# Logic.net
KiCad netlist of a schematic drawn in Altium Designer
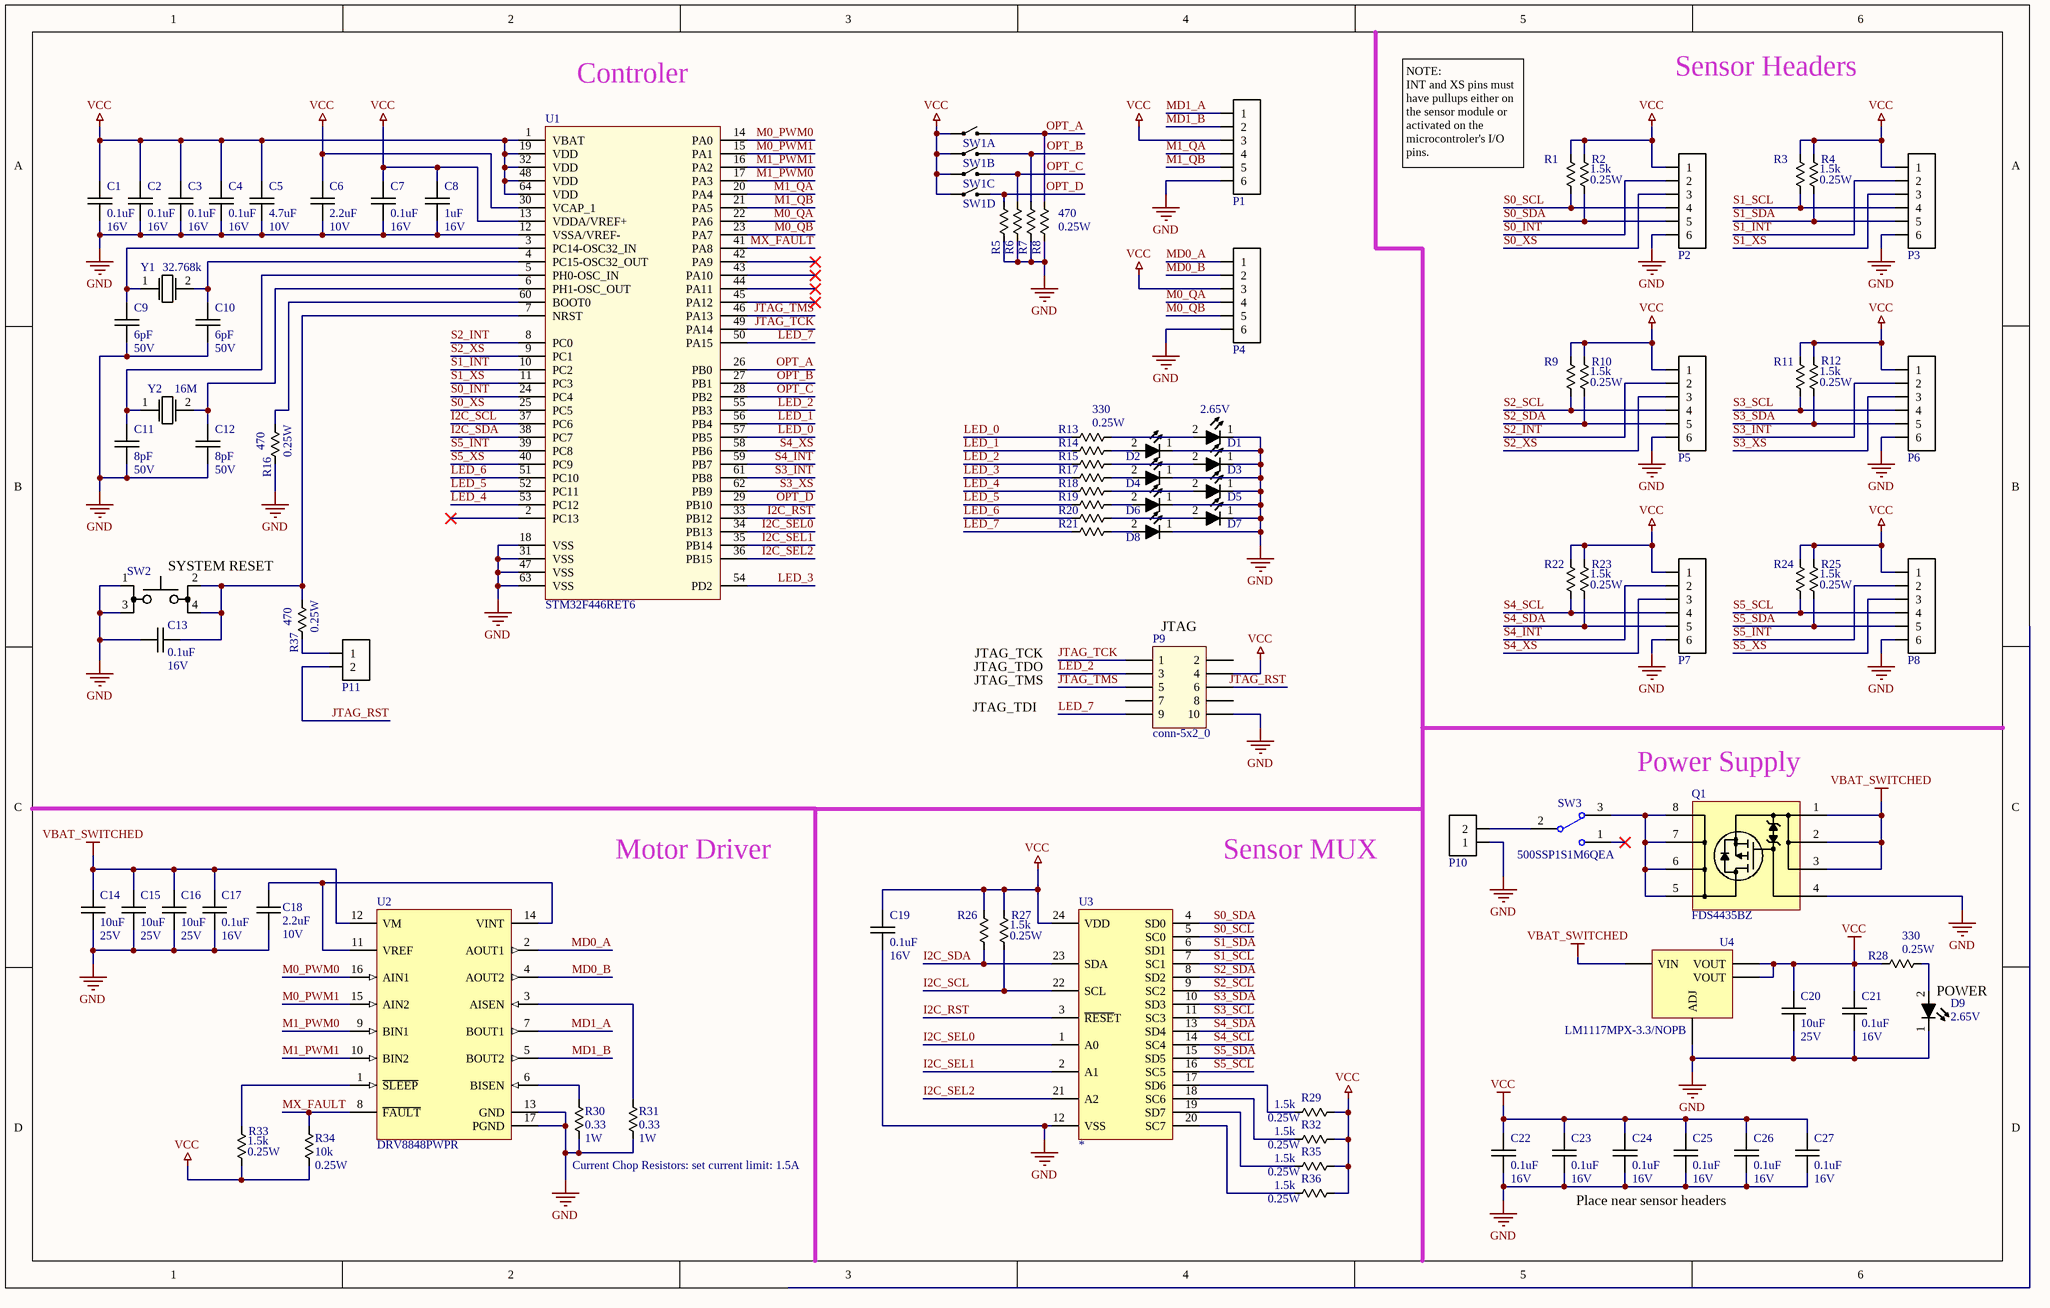
[diagram p0: Logic.SchDoc]

(export (version "E")
  (design (tool "Eeschema 10.0.6"))
  (components
    (comp (ref "C1")
      (value "cap_single_np")
      (footprint "chip_0603")
      (description "CAP, 0.1uF, ±10%, 16V, X7R, 0603")
      (fields
        (field (name "TOLERANCE") "±10%")
        (field (name "CAPACITANCE") "0.1uF")
        (field (name "VOLTAGE RATING") "16V")
        (field (name "PART NUMBER") "CAP-00542")
      )
      (libsource (lib "Capacitors") (part "cap_single_np"))
    )
    (comp (ref "C2")
      (value "cap_single_np")
      (footprint "chip_0603")
      (description "CAP, 0.1uF, ±10%, 16V, X7R, 0603")
      (fields
        (field (name "TOLERANCE") "±10%")
        (field (name "CAPACITANCE") "0.1uF")
        (field (name "VOLTAGE RATING") "16V")
        (field (name "PART NUMBER") "CAP-00542")
      )
      (libsource (lib "Capacitors") (part "cap_single_np"))
    )
    (comp (ref "C3")
      (value "cap_single_np")
      (footprint "chip_0603")
      (description "CAP, 0.1uF, ±10%, 16V, X7R, 0603")
      (fields
        (field (name "TOLERANCE") "±10%")
        (field (name "CAPACITANCE") "0.1uF")
        (field (name "VOLTAGE RATING") "16V")
        (field (name "PART NUMBER") "CAP-00542")
      )
      (libsource (lib "Capacitors") (part "cap_single_np"))
    )
    (comp (ref "C4")
      (value "cap_single_np")
      (footprint "chip_0603")
      (description "CAP, 0.1uF, ±10%, 16V, X7R, 0603")
      (fields
        (field (name "TOLERANCE") "±10%")
        (field (name "CAPACITANCE") "0.1uF")
        (field (name "VOLTAGE RATING") "16V")
        (field (name "PART NUMBER") "CAP-00542")
      )
      (libsource (lib "Capacitors") (part "cap_single_np"))
    )
    (comp (ref "C5")
      (value "cap_single_np")
      (footprint "chip_0805")
      (description "CAP, 4.7uF, 10%, 10V, X7R, 0805")
      (fields
        (field (name "TOLERANCE") "10%")
        (field (name "CAPACITANCE") "4.7uF")
        (field (name "VOLTAGE RATING") "10V")
        (field (name "PART NUMBER") "CAP-00126")
      )
      (libsource (lib "Capacitors") (part "cap_single_np"))
    )
    (comp (ref "C6")
      (value "cap_single_np")
      (footprint "chip_0603")
      (description "CAP, 2.2uF, ±10%, 10V, X7R, 0603")
      (fields
        (field (name "TOLERANCE") "±10%")
        (field (name "CAPACITANCE") "2.2uF")
        (field (name "VOLTAGE RATING") "10V")
        (field (name "PART NUMBER") "CAP-00531")
      )
      (libsource (lib "Capacitors") (part "cap_single_np"))
    )
    (comp (ref "C7")
      (value "cap_single_np")
      (footprint "chip_0603")
      (description "CAP, 0.1uF, ±10%, 16V, X7R, 0603")
      (fields
        (field (name "TOLERANCE") "±10%")
        (field (name "CAPACITANCE") "0.1uF")
        (field (name "VOLTAGE RATING") "16V")
        (field (name "PART NUMBER") "CAP-00542")
      )
      (libsource (lib "Capacitors") (part "cap_single_np"))
    )
    (comp (ref "C8")
      (value "cap_single_np")
      (footprint "chip_0805")
      (description "CAP, 1uF, 10%, 16V, X7R, 0805")
      (fields
        (field (name "TOLERANCE") "10%")
        (field (name "CAPACITANCE") "1uF")
        (field (name "VOLTAGE RATING") "16V")
        (field (name "PART NUMBER") "CAP-00107")
      )
      (libsource (lib "Capacitors") (part "cap_single_np"))
    )
    (comp (ref "C9")
      (value "cap_single_np")
      (footprint "chip_0603")
      (description "CAP, 6pF, ±10%, 50V, C0G, 0603")
      (fields
        (field (name "TOLERANCE") "±10%")
        (field (name "CAPACITANCE") "6pF")
        (field (name "VOLTAGE RATING") "50V")
        (field (name "PART NUMBER") "CAP-00538")
      )
      (libsource (lib "Capacitors") (part "cap_single_np"))
    )
    (comp (ref "C10")
      (value "cap_single_np")
      (footprint "chip_0603")
      (description "CAP, 6pF, ±10%, 50V, C0G, 0603")
      (fields
        (field (name "TOLERANCE") "±10%")
        (field (name "CAPACITANCE") "6pF")
        (field (name "VOLTAGE RATING") "50V")
        (field (name "PART NUMBER") "CAP-00538")
      )
      (libsource (lib "Capacitors") (part "cap_single_np"))
    )
    (comp (ref "C11")
      (value "cap_single_np")
      (footprint "chip_0603")
      (description "CAP, 8pF, ±0.1pF, 50V, C0G, 0603")
      (fields
        (field (name "TOLERANCE") "±0.1pF")
        (field (name "CAPACITANCE") "8pF")
        (field (name "VOLTAGE RATING") "50V")
        (field (name "PART NUMBER") "CAP-00402")
      )
      (libsource (lib "Capacitors") (part "cap_single_np"))
    )
    (comp (ref "C12")
      (value "cap_single_np")
      (footprint "chip_0603")
      (description "CAP, 8pF, ±0.1pF, 50V, C0G, 0603")
      (fields
        (field (name "TOLERANCE") "±0.1pF")
        (field (name "CAPACITANCE") "8pF")
        (field (name "VOLTAGE RATING") "50V")
        (field (name "PART NUMBER") "CAP-00402")
      )
      (libsource (lib "Capacitors") (part "cap_single_np"))
    )
    (comp (ref "C13")
      (value "cap_single_np")
      (footprint "chip_0603")
      (description "CAP, 0.1uF, ±10%, 16V, X7R, 0603")
      (fields
        (field (name "TOLERANCE") "±10%")
        (field (name "CAPACITANCE") "0.1uF")
        (field (name "VOLTAGE RATING") "16V")
        (field (name "PART NUMBER") "CAP-00542")
      )
      (libsource (lib "Capacitors") (part "cap_single_np"))
    )
    (comp (ref "C14")
      (value "cap_single_np")
      (footprint "chip_1206")
      (description "CAP, 10uF, ±10%, 25V, X7R, 1206")
      (fields
        (field (name "TOLERANCE") "±10%")
        (field (name "CAPACITANCE") "10uF")
        (field (name "VOLTAGE RATING") "25V")
        (field (name "PART NUMBER") "CAP-00539")
      )
      (libsource (lib "Capacitors") (part "cap_single_np"))
    )
    (comp (ref "C15")
      (value "cap_single_np")
      (footprint "chip_1206")
      (description "CAP, 10uF, ±10%, 25V, X7R, 1206")
      (fields
        (field (name "TOLERANCE") "±10%")
        (field (name "CAPACITANCE") "10uF")
        (field (name "VOLTAGE RATING") "25V")
        (field (name "PART NUMBER") "CAP-00539")
      )
      (libsource (lib "Capacitors") (part "cap_single_np"))
    )
    (comp (ref "C16")
      (value "cap_single_np")
      (footprint "chip_1206")
      (description "CAP, 10uF, ±10%, 25V, X7R, 1206")
      (fields
        (field (name "TOLERANCE") "±10%")
        (field (name "CAPACITANCE") "10uF")
        (field (name "VOLTAGE RATING") "25V")
        (field (name "PART NUMBER") "CAP-00539")
      )
      (libsource (lib "Capacitors") (part "cap_single_np"))
    )
    (comp (ref "C17")
      (value "cap_single_np")
      (footprint "chip_0603")
      (description "CAP, 0.1uF, ±10%, 16V, X7R, 0603")
      (fields
        (field (name "TOLERANCE") "±10%")
        (field (name "CAPACITANCE") "0.1uF")
        (field (name "VOLTAGE RATING") "16V")
        (field (name "PART NUMBER") "CAP-00542")
      )
      (libsource (lib "Capacitors") (part "cap_single_np"))
    )
    (comp (ref "C18")
      (value "cap_single_np")
      (footprint "chip_0603")
      (description "CAP, 2.2uF, ±10%, 10V, X7R, 0603")
      (fields
        (field (name "TOLERANCE") "±10%")
        (field (name "CAPACITANCE") "2.2uF")
        (field (name "VOLTAGE RATING") "10V")
        (field (name "PART NUMBER") "CAP-00531")
      )
      (libsource (lib "Capacitors") (part "cap_single_np"))
    )
    (comp (ref "C19")
      (value "cap_single_np")
      (footprint "chip_0603")
      (description "CAP, 0.1uF, ±10%, 16V, X7R, 0603")
      (fields
        (field (name "TOLERANCE") "±10%")
        (field (name "CAPACITANCE") "0.1uF")
        (field (name "VOLTAGE RATING") "16V")
        (field (name "PART NUMBER") "CAP-00542")
      )
      (libsource (lib "Capacitors") (part "cap_single_np"))
    )
    (comp (ref "C20")
      (value "cap_single_np")
      (footprint "chip_1206")
      (description "CAP, 10uF, ±10%, 25V, X7R, 1206")
      (fields
        (field (name "TOLERANCE") "±10%")
        (field (name "CAPACITANCE") "10uF")
        (field (name "VOLTAGE RATING") "25V")
        (field (name "PART NUMBER") "CAP-00539")
      )
      (libsource (lib "Capacitors") (part "cap_single_np"))
    )
    (comp (ref "C21")
      (value "cap_single_np")
      (footprint "chip_0603")
      (description "CAP, 0.1uF, ±10%, 16V, X7R, 0603")
      (fields
        (field (name "TOLERANCE") "±10%")
        (field (name "CAPACITANCE") "0.1uF")
        (field (name "VOLTAGE RATING") "16V")
        (field (name "PART NUMBER") "CAP-00542")
      )
      (libsource (lib "Capacitors") (part "cap_single_np"))
    )
    (comp (ref "C22")
      (value "cap_single_np")
      (footprint "chip_0603")
      (description "CAP, 0.1uF, ±10%, 16V, X7R, 0603")
      (fields
        (field (name "TOLERANCE") "±10%")
        (field (name "CAPACITANCE") "0.1uF")
        (field (name "VOLTAGE RATING") "16V")
        (field (name "PART NUMBER") "CAP-00542")
      )
      (libsource (lib "Capacitors") (part "cap_single_np"))
    )
    (comp (ref "C23")
      (value "cap_single_np")
      (footprint "chip_0603")
      (description "CAP, 0.1uF, ±10%, 16V, X7R, 0603")
      (fields
        (field (name "TOLERANCE") "±10%")
        (field (name "CAPACITANCE") "0.1uF")
        (field (name "VOLTAGE RATING") "16V")
        (field (name "PART NUMBER") "CAP-00542")
      )
      (libsource (lib "Capacitors") (part "cap_single_np"))
    )
    (comp (ref "C24")
      (value "cap_single_np")
      (footprint "chip_0603")
      (description "CAP, 0.1uF, ±10%, 16V, X7R, 0603")
      (fields
        (field (name "TOLERANCE") "±10%")
        (field (name "CAPACITANCE") "0.1uF")
        (field (name "VOLTAGE RATING") "16V")
        (field (name "PART NUMBER") "CAP-00542")
      )
      (libsource (lib "Capacitors") (part "cap_single_np"))
    )
    (comp (ref "C25")
      (value "cap_single_np")
      (footprint "chip_0603")
      (description "CAP, 0.1uF, ±10%, 16V, X7R, 0603")
      (fields
        (field (name "TOLERANCE") "±10%")
        (field (name "CAPACITANCE") "0.1uF")
        (field (name "VOLTAGE RATING") "16V")
        (field (name "PART NUMBER") "CAP-00542")
      )
      (libsource (lib "Capacitors") (part "cap_single_np"))
    )
    (comp (ref "C26")
      (value "cap_single_np")
      (footprint "chip_0603")
      (description "CAP, 0.1uF, ±10%, 16V, X7R, 0603")
      (fields
        (field (name "TOLERANCE") "±10%")
        (field (name "CAPACITANCE") "0.1uF")
        (field (name "VOLTAGE RATING") "16V")
        (field (name "PART NUMBER") "CAP-00542")
      )
      (libsource (lib "Capacitors") (part "cap_single_np"))
    )
    (comp (ref "C27")
      (value "cap_single_np")
      (footprint "chip_0603")
      (description "CAP, 0.1uF, ±10%, 16V, X7R, 0603")
      (fields
        (field (name "TOLERANCE") "±10%")
        (field (name "CAPACITANCE") "0.1uF")
        (field (name "VOLTAGE RATING") "16V")
        (field (name "PART NUMBER") "CAP-00542")
      )
      (libsource (lib "Capacitors") (part "cap_single_np"))
    )
    (comp (ref "D1")
      (value "diode_4")
      (footprint "chip_0603")
      (description "LED, Green, 0603, Low current, HELI2 Series")
      (fields
        (field (name "FORWARD VOLTAGE") "2.65V")
        (field (name "PART NUMBER") "DIO-00050")
        (field (name "MANUFACTURER") "Kingbright")
      )
      (libsource (lib "Diodes") (part "diode_4"))
    )
    (comp (ref "D2")
      (value "diode_4")
      (footprint "chip_0603")
      (description "LED, Green, 0603, Low current, HELI2 Series")
      (fields (field (name "PART NUMBER") "DIO-00050") (field (name "MANUFACTURER") "Kingbright"))
      (libsource (lib "Diodes") (part "diode_4"))
    )
    (comp (ref "D3")
      (value "diode_4")
      (footprint "chip_0603")
      (description "LED, Green, 0603, Low current, HELI2 Series")
      (fields (field (name "PART NUMBER") "DIO-00050") (field (name "MANUFACTURER") "Kingbright"))
      (libsource (lib "Diodes") (part "diode_4"))
    )
    (comp (ref "D4")
      (value "diode_4")
      (footprint "chip_0603")
      (description "LED, Green, 0603, Low current, HELI2 Series")
      (fields (field (name "PART NUMBER") "DIO-00050") (field (name "MANUFACTURER") "Kingbright"))
      (libsource (lib "Diodes") (part "diode_4"))
    )
    (comp (ref "D5")
      (value "diode_4")
      (footprint "chip_0603")
      (description "LED, Green, 0603, Low current, HELI2 Series")
      (fields (field (name "PART NUMBER") "DIO-00050") (field (name "MANUFACTURER") "Kingbright"))
      (libsource (lib "Diodes") (part "diode_4"))
    )
    (comp (ref "D6")
      (value "diode_4")
      (footprint "chip_0603")
      (description "LED, Green, 0603, Low current, HELI2 Series")
      (fields (field (name "PART NUMBER") "DIO-00050") (field (name "MANUFACTURER") "Kingbright"))
      (libsource (lib "Diodes") (part "diode_4"))
    )
    (comp (ref "D7")
      (value "diode_4")
      (footprint "chip_0603")
      (description "LED, Green, 0603, Low current, HELI2 Series")
      (fields (field (name "PART NUMBER") "DIO-00050") (field (name "MANUFACTURER") "Kingbright"))
      (libsource (lib "Diodes") (part "diode_4"))
    )
    (comp (ref "D8")
      (value "diode_4")
      (footprint "chip_0603")
      (description "LED, Green, 0603, Low current, HELI2 Series")
      (fields (field (name "PART NUMBER") "DIO-00050") (field (name "MANUFACTURER") "Kingbright"))
      (libsource (lib "Diodes") (part "diode_4"))
    )
    (comp (ref "D9")
      (value "diode_4")
      (footprint "chip_0603")
      (description "LED, Blue, 0603, Low current, HELI2 Series")
      (fields
        (field (name "FORWARD VOLTAGE") "2.65V")
        (field (name "PART NUMBER") "DIO-00049")
        (field (name "MANUFACTURER") "Kingbright")
      )
      (libsource (lib "Diodes") (part "diode_4"))
    )
    (comp (ref "P1")
      (value "conn-6x1_0")
      (footprint "JST_PHR_6_0")
      (description "JST PHR 6x1")
      (fields (field (name "PART NUMBER") "CONN-00017") (field (name "MANUFACTURER") "JST"))
      (libsource (lib "Connectors") (part "conn-6x1_0"))
    )
    (comp (ref "P2")
      (value "conn-6x1_0")
      (footprint "HDDR_6X1_0")
      (description "Header 6x1, 0.1\"")
      (fields (field (name "PART NUMBER") "CONN-00008"))
      (libsource (lib "Connectors") (part "conn-6x1_0"))
    )
    (comp (ref "P3")
      (value "conn-6x1_0")
      (footprint "HDDR_6X1_0")
      (description "Header 6x1, 0.1\"")
      (fields (field (name "PART NUMBER") "CONN-00008"))
      (libsource (lib "Connectors") (part "conn-6x1_0"))
    )
    (comp (ref "P4")
      (value "conn-6x1_0")
      (footprint "JST_PHR_6_0")
      (description "JST PHR 6x1")
      (fields (field (name "PART NUMBER") "CONN-00017") (field (name "MANUFACTURER") "JST"))
      (libsource (lib "Connectors") (part "conn-6x1_0"))
    )
    (comp (ref "P5")
      (value "conn-6x1_0")
      (footprint "HDDR_6X1_0")
      (description "Header 6x1, 0.1\"")
      (fields (field (name "PART NUMBER") "CONN-00008"))
      (libsource (lib "Connectors") (part "conn-6x1_0"))
    )
    (comp (ref "P6")
      (value "conn-6x1_0")
      (footprint "HDDR_6X1_0")
      (description "Header 6x1, 0.1\"")
      (fields (field (name "PART NUMBER") "CONN-00008"))
      (libsource (lib "Connectors") (part "conn-6x1_0"))
    )
    (comp (ref "P7")
      (value "conn-6x1_0")
      (footprint "HDDR_6X1_0")
      (description "Header 6x1, 0.1\"")
      (fields (field (name "PART NUMBER") "CONN-00008"))
      (libsource (lib "Connectors") (part "conn-6x1_0"))
    )
    (comp (ref "P8")
      (value "conn-6x1_0")
      (footprint "HDDR_6X1_0")
      (description "Header 6x1, 0.1\"")
      (fields (field (name "PART NUMBER") "CONN-00008"))
      (libsource (lib "Connectors") (part "conn-6x1_0"))
    )
    (comp (ref "P9")
      (value "conn-5x2_0")
      (footprint "CNC_TECH_3020-10-0100-XX")
      (description "Header, 10-pin IDC, 2.54mm Pitch")
      (fields (field (name "PART NUMBER") "CONN-00054") (field (name "MANUFACTURER") "CNC Tech"))
      (libsource (lib "Connectors") (part "conn-5x2_0"))
    )
    (comp (ref "P10")
      (value "conn-2x1_0")
      (footprint "PHOENIX_MKDS_5.08MM_2x1")
      (description "Term Blk, 2 Pos, 0.2\", 10A, 14-30 AWG, Rising Cage Clamp")
      (fields (field (name "PART NUMBER") "CONN-00014") (field (name "MANUFACTURER") "Phoenix Contact"))
      (libsource (lib "Connectors") (part "conn-2x1_0"))
    )
    (comp (ref "P11")
      (value "conn-2x1_0")
      (footprint "hddr_2x1_0")
      (description "Header, 2x1, 0.1\"")
      (fields (field (name "PART NUMBER") "CONN-00055") (field (name "MANUFACTURER") "Samtec"))
      (libsource (lib "Connectors") (part "conn-2x1_0"))
    )
    (comp (ref "Q1")
      (value "p-mosfet-SSSGDDDD")
      (footprint "SO-8")
      (description "XSTR PFET, 8.8A, 30V, 2.5W, SOIC-8")
      (fields
        (field (name "MANUFACTURER PN") "FDS4435BZ")
        (field (name "PART NUMBER") "XSTR-00033")
        (field (name "MANUFACTURER") "ON Semi")
      )
      (libsource (lib "Transistors") (part "p-mosfet-SSSGDDDD"))
    )
    (comp (ref "R1")
      (value "res_single")
      (footprint "chip_0603")
      (description "RES SMD 1.5K OHM 1% 1/4W 0603")
      (fields (field (name "TOLERANCE") "1%") (field (name "PART NUMBER") "RES-00284"))
      (libsource (lib "Resistors") (part "res_single"))
    )
    (comp (ref "R2")
      (value "res_single")
      (footprint "chip_0603")
      (description "RES SMD 1.5K OHM 1% 1/4W 0603")
      (fields
        (field (name "TOLERANCE") "1%")
        (field (name "RESISTANCE") "1.5k")
        (field (name "POWER RATING") "0.25W")
        (field (name "PART NUMBER") "RES-00284")
      )
      (libsource (lib "Resistors") (part "res_single"))
    )
    (comp (ref "R3")
      (value "res_single")
      (footprint "chip_0603")
      (description "RES SMD 1.5K OHM 1% 1/4W 0603")
      (fields (field (name "TOLERANCE") "1%") (field (name "PART NUMBER") "RES-00284"))
      (libsource (lib "Resistors") (part "res_single"))
    )
    (comp (ref "R4")
      (value "res_single")
      (footprint "chip_0603")
      (description "RES SMD 1.5K OHM 1% 1/4W 0603")
      (fields
        (field (name "TOLERANCE") "1%")
        (field (name "RESISTANCE") "1.5k")
        (field (name "POWER RATING") "0.25W")
        (field (name "PART NUMBER") "RES-00284")
      )
      (libsource (lib "Resistors") (part "res_single"))
    )
    (comp (ref "R5")
      (value "res_single")
      (footprint "chip_0603")
      (description "RES SMD 470 OHM 1% 1/4W 0603")
      (fields (field (name "TOLERANCE") "1%") (field (name "PART NUMBER") "RES-00236"))
      (libsource (lib "Resistors") (part "res_single"))
    )
    (comp (ref "R6")
      (value "res_single")
      (footprint "chip_0603")
      (description "RES SMD 470 OHM 1% 1/4W 0603")
      (fields (field (name "TOLERANCE") "1%") (field (name "PART NUMBER") "RES-00236"))
      (libsource (lib "Resistors") (part "res_single"))
    )
    (comp (ref "R7")
      (value "res_single")
      (footprint "chip_0603")
      (description "RES SMD 470 OHM 1% 1/4W 0603")
      (fields (field (name "TOLERANCE") "1%") (field (name "PART NUMBER") "RES-00236"))
      (libsource (lib "Resistors") (part "res_single"))
    )
    (comp (ref "R8")
      (value "res_single")
      (footprint "chip_0603")
      (description "RES SMD 470 OHM 1% 1/4W 0603")
      (fields
        (field (name "TOLERANCE") "1%")
        (field (name "RESISTANCE") "470")
        (field (name "POWER RATING") "0.25W")
        (field (name "PART NUMBER") "RES-00236")
      )
      (libsource (lib "Resistors") (part "res_single"))
    )
    (comp (ref "R9")
      (value "res_single")
      (footprint "chip_0603")
      (description "RES SMD 1.5K OHM 1% 1/4W 0603")
      (fields (field (name "TOLERANCE") "1%") (field (name "PART NUMBER") "RES-00284"))
      (libsource (lib "Resistors") (part "res_single"))
    )
    (comp (ref "R10")
      (value "res_single")
      (footprint "chip_0603")
      (description "RES SMD 1.5K OHM 1% 1/4W 0603")
      (fields
        (field (name "TOLERANCE") "1%")
        (field (name "RESISTANCE") "1.5k")
        (field (name "POWER RATING") "0.25W")
        (field (name "PART NUMBER") "RES-00284")
      )
      (libsource (lib "Resistors") (part "res_single"))
    )
    (comp (ref "R11")
      (value "res_single")
      (footprint "chip_0603")
      (description "RES SMD 1.5K OHM 1% 1/4W 0603")
      (fields (field (name "TOLERANCE") "1%") (field (name "PART NUMBER") "RES-00284"))
      (libsource (lib "Resistors") (part "res_single"))
    )
    (comp (ref "R12")
      (value "res_single")
      (footprint "chip_0603")
      (description "RES SMD 1.5K OHM 1% 1/4W 0603")
      (fields
        (field (name "TOLERANCE") "1%")
        (field (name "RESISTANCE") "1.5k")
        (field (name "POWER RATING") "0.25W")
        (field (name "PART NUMBER") "RES-00284")
      )
      (libsource (lib "Resistors") (part "res_single"))
    )
    (comp (ref "R13")
      (value "res_single")
      (footprint "chip_0603")
      (description "RES SMD 330 OHM 1% 1/4W 0603")
      (fields
        (field (name "TOLERANCE") "1%")
        (field (name "RESISTANCE") "330")
        (field (name "POWER RATING") "0.25W")
        (field (name "PART NUMBER") "RES-00221")
      )
      (libsource (lib "Resistors") (part "res_single"))
    )
    (comp (ref "R14")
      (value "res_single")
      (footprint "chip_0603")
      (description "RES SMD 330 OHM 1% 1/4W 0603")
      (fields (field (name "TOLERANCE") "1%") (field (name "PART NUMBER") "RES-00221"))
      (libsource (lib "Resistors") (part "res_single"))
    )
    (comp (ref "R15")
      (value "res_single")
      (footprint "chip_0603")
      (description "RES SMD 330 OHM 1% 1/4W 0603")
      (fields (field (name "TOLERANCE") "1%") (field (name "PART NUMBER") "RES-00221"))
      (libsource (lib "Resistors") (part "res_single"))
    )
    (comp (ref "R16")
      (value "res_single")
      (footprint "chip_0603")
      (description "RES SMD 470 OHM 1% 1/4W 0603")
      (fields
        (field (name "TOLERANCE") "1%")
        (field (name "RESISTANCE") "470")
        (field (name "POWER RATING") "0.25W")
        (field (name "PART NUMBER") "RES-00236")
      )
      (libsource (lib "Resistors") (part "res_single"))
    )
    (comp (ref "R17")
      (value "res_single")
      (footprint "chip_0603")
      (description "RES SMD 330 OHM 1% 1/4W 0603")
      (fields (field (name "TOLERANCE") "1%") (field (name "PART NUMBER") "RES-00221"))
      (libsource (lib "Resistors") (part "res_single"))
    )
    (comp (ref "R18")
      (value "res_single")
      (footprint "chip_0603")
      (description "RES SMD 330 OHM 1% 1/4W 0603")
      (fields (field (name "TOLERANCE") "1%") (field (name "PART NUMBER") "RES-00221"))
      (libsource (lib "Resistors") (part "res_single"))
    )
    (comp (ref "R19")
      (value "res_single")
      (footprint "chip_0603")
      (description "RES SMD 330 OHM 1% 1/4W 0603")
      (fields (field (name "TOLERANCE") "1%") (field (name "PART NUMBER") "RES-00221"))
      (libsource (lib "Resistors") (part "res_single"))
    )
    (comp (ref "R20")
      (value "res_single")
      (footprint "chip_0603")
      (description "RES SMD 330 OHM 1% 1/4W 0603")
      (fields (field (name "TOLERANCE") "1%") (field (name "PART NUMBER") "RES-00221"))
      (libsource (lib "Resistors") (part "res_single"))
    )
    (comp (ref "R21")
      (value "res_single")
      (footprint "chip_0603")
      (description "RES SMD 330 OHM 1% 1/4W 0603")
      (fields (field (name "TOLERANCE") "1%") (field (name "PART NUMBER") "RES-00221"))
      (libsource (lib "Resistors") (part "res_single"))
    )
    (comp (ref "R22")
      (value "res_single")
      (footprint "chip_0603")
      (description "RES SMD 1.5K OHM 1% 1/4W 0603")
      (fields (field (name "TOLERANCE") "1%") (field (name "PART NUMBER") "RES-00284"))
      (libsource (lib "Resistors") (part "res_single"))
    )
    (comp (ref "R23")
      (value "res_single")
      (footprint "chip_0603")
      (description "RES SMD 1.5K OHM 1% 1/4W 0603")
      (fields
        (field (name "TOLERANCE") "1%")
        (field (name "RESISTANCE") "1.5k")
        (field (name "POWER RATING") "0.25W")
        (field (name "PART NUMBER") "RES-00284")
      )
      (libsource (lib "Resistors") (part "res_single"))
    )
    (comp (ref "R24")
      (value "res_single")
      (footprint "chip_0603")
      (description "RES SMD 1.5K OHM 1% 1/4W 0603")
      (fields (field (name "TOLERANCE") "1%") (field (name "PART NUMBER") "RES-00284"))
      (libsource (lib "Resistors") (part "res_single"))
    )
    (comp (ref "R25")
      (value "res_single")
      (footprint "chip_0603")
      (description "RES SMD 1.5K OHM 1% 1/4W 0603")
      (fields
        (field (name "TOLERANCE") "1%")
        (field (name "RESISTANCE") "1.5k")
        (field (name "POWER RATING") "0.25W")
        (field (name "PART NUMBER") "RES-00284")
      )
      (libsource (lib "Resistors") (part "res_single"))
    )
    (comp (ref "R26")
      (value "res_single")
      (footprint "chip_0603")
      (description "RES SMD 1.5K OHM 1% 1/4W 0603")
      (fields (field (name "TOLERANCE") "1%") (field (name "PART NUMBER") "RES-00284"))
      (libsource (lib "Resistors") (part "res_single"))
    )
    (comp (ref "R27")
      (value "res_single")
      (footprint "chip_0603")
      (description "RES SMD 1.5K OHM 1% 1/4W 0603")
      (fields
        (field (name "TOLERANCE") "1%")
        (field (name "RESISTANCE") "1.5k")
        (field (name "POWER RATING") "0.25W")
        (field (name "PART NUMBER") "RES-00284")
      )
      (libsource (lib "Resistors") (part "res_single"))
    )
    (comp (ref "R28")
      (value "res_single")
      (footprint "chip_0603")
      (description "RES SMD 330 OHM 1% 1/4W 0603")
      (fields
        (field (name "TOLERANCE") "1%")
        (field (name "RESISTANCE") "330")
        (field (name "POWER RATING") "0.25W")
        (field (name "PART NUMBER") "RES-00221")
      )
      (libsource (lib "Resistors") (part "res_single"))
    )
    (comp (ref "R29")
      (value "res_single")
      (footprint "chip_0603")
      (description "RES SMD 1.5K OHM 1% 1/4W 0603")
      (fields
        (field (name "TOLERANCE") "1%")
        (field (name "RESISTANCE") "1.5k")
        (field (name "POWER RATING") "0.25W")
        (field (name "PART NUMBER") "RES-00284")
      )
      (libsource (lib "Resistors") (part "res_single"))
    )
    (comp (ref "R30")
      (value "res_single")
      (footprint "chip_2512")
      (description "RES SMD 0.33 OHM 1% 1W 2512")
      (fields
        (field (name "TOLERANCE") "1%")
        (field (name "RESISTANCE") "0.33")
        (field (name "POWER RATING") "1W")
        (field (name "PART NUMBER") "RES-00692")
      )
      (libsource (lib "Resistors") (part "res_single"))
    )
    (comp (ref "R31")
      (value "res_single")
      (footprint "chip_2512")
      (description "RES SMD 0.33 OHM 1% 1W 2512")
      (fields
        (field (name "TOLERANCE") "1%")
        (field (name "RESISTANCE") "0.33")
        (field (name "POWER RATING") "1W")
        (field (name "PART NUMBER") "RES-00692")
      )
      (libsource (lib "Resistors") (part "res_single"))
    )
    (comp (ref "R32")
      (value "res_single")
      (footprint "chip_0603")
      (description "RES SMD 1.5K OHM 1% 1/4W 0603")
      (fields
        (field (name "TOLERANCE") "1%")
        (field (name "RESISTANCE") "1.5k")
        (field (name "POWER RATING") "0.25W")
        (field (name "PART NUMBER") "RES-00284")
      )
      (libsource (lib "Resistors") (part "res_single"))
    )
    (comp (ref "R33")
      (value "res_single")
      (footprint "chip_0603")
      (description "RES SMD 1.5K OHM 1% 1/4W 0603")
      (fields
        (field (name "TOLERANCE") "1%")
        (field (name "RESISTANCE") "1.5k")
        (field (name "POWER RATING") "0.25W")
        (field (name "PART NUMBER") "RES-00284")
      )
      (libsource (lib "Resistors") (part "res_single"))
    )
    (comp (ref "R34")
      (value "res_single")
      (footprint "chip_0603")
      (description "RES SMD 10K OHM 1% 1/4W 0603")
      (fields
        (field (name "TOLERANCE") "1%")
        (field (name "RESISTANCE") "10k")
        (field (name "POWER RATING") "0.25W")
        (field (name "PART NUMBER") "RES-00306")
      )
      (libsource (lib "Resistors") (part "res_single"))
    )
    (comp (ref "R35")
      (value "res_single")
      (footprint "chip_0603")
      (description "RES SMD 1.5K OHM 1% 1/4W 0603")
      (fields
        (field (name "TOLERANCE") "1%")
        (field (name "RESISTANCE") "1.5k")
        (field (name "POWER RATING") "0.25W")
        (field (name "PART NUMBER") "RES-00284")
      )
      (libsource (lib "Resistors") (part "res_single"))
    )
    (comp (ref "R36")
      (value "res_single")
      (footprint "chip_0603")
      (description "RES SMD 1.5K OHM 1% 1/4W 0603")
      (fields
        (field (name "TOLERANCE") "1%")
        (field (name "RESISTANCE") "1.5k")
        (field (name "POWER RATING") "0.25W")
        (field (name "PART NUMBER") "RES-00284")
      )
      (libsource (lib "Resistors") (part "res_single"))
    )
    (comp (ref "R37")
      (value "res_single")
      (footprint "chip_0603")
      (description "RES SMD 470 OHM 1% 1/4W 0603")
      (fields
        (field (name "TOLERANCE") "1%")
        (field (name "RESISTANCE") "470")
        (field (name "POWER RATING") "0.25W")
        (field (name "PART NUMBER") "RES-00236")
      )
      (libsource (lib "Resistors") (part "res_single"))
    )
    (comp (ref "SW1")
      (value "DIP_SW_4")
      (footprint "A6S-4104-H")
      (description "DIP Switch, SMD, 25mA, 24V")
      (fields (field (name "PART NUMBER") "MISC-00026") (field (name "MANUFACTURER") "Omron"))
      (libsource (lib "Misc") (part "DIP_SW_4"))
    )
    (comp (ref "SW2")
      (value "SW_1P1T_0")
      (footprint "KMR6")
      (description "Switch, SPST, Tactile, 32V 50mA")
      (fields (field (name "PART NUMBER") "MISC-00024") (field (name "MANUFACTURER") "C&K"))
      (libsource (lib "Misc") (part "SW_1P1T_0"))
    )
    (comp (ref "SW3")
      (value "SW-SPDT")
      (footprint "E-Switch_500SSPyS1M6yEA")
      (description "Switch, SPDT, 120VAC/28VDC, 5A, Horizontal Slide Switch")
      (fields
        (field (name "MANUFACTURER PN") "500SSP1S1M6QEA")
        (field (name "PART NUMBER") "MISC-00033")
        (field (name "MANUFACTURER") "E-Switch")
      )
      (libsource (lib "Misc") (part "SW-SPDT"))
    )
    (comp (ref "U1")
      (value "STM32F446_64_0")
      (footprint "LQFP64_0")
      (description "STM32F4 Series, 32-bit ARM M4, 180MHz, LQFP64")
      (fields
        (field (name "MANUFACTURER PN") "STM32F446RET6")
        (field (name "PART NUMBER") "UCTRL-00002")
        (field (name "MANUFACTURER") "ST")
      )
      (libsource (lib "Microcontrollers") (part "STM32F446_64_0"))
    )
    (comp (ref "U2")
      (value "DRV8848")
      (footprint "HTSSOP-16_0")
      (description "IC, Motor Driver, Quad Half-Bridge, 4-18V")
      (fields
        (field (name "MANUFACTURER PN") "DRV8848PWPR")
        (field (name "PART NUMBER") "MISC-00022")
        (field (name "MANUFACTURER") "TI")
      )
      (libsource (lib "Misc") (part "DRV8848"))
    )
    (comp (ref "U3")
      (value "TCA9548A")
      (footprint "tssop-24_0")
      (description "I2C 8-Channel Mux with Reset, TCA9548A")
      (fields
        (field (name "MANUFACTURE PN") "*")
        (field (name "PART NUMBER") "IFACE-00001")
        (field (name "MANUFACTURER") "TI")
      )
      (libsource (lib "Interfaces") (part "TCA9548A"))
    )
    (comp (ref "U4")
      (value "LM1117")
      (footprint "sot-223-4")
      (description "REG, Linear, Fixed 3V3, 800mA, SOT-223")
      (fields
        (field (name "MANUFACTURER PN") "LM1117MPX-3.3/NOPB")
        (field (name "PART NUMBER") "PWREG-00018")
        (field (name "MANUFACTURER") "TI")
      )
      (libsource (lib "Power Reg") (part "LM1117"))
    )
    (comp (ref "Y1")
      (value "osc_xtal_2p_0")
      (footprint "ABS25_OSC")
      (description "XTAL, 32.768kHz, 6pF, 20ppm")
      (fields
        (field (name "TOLERANCE") "20ppm")
        (field (name "FREQUENCY") "32.768k")
        (field (name "PART NUMBER") "OSC-00003")
      )
      (libsource (lib "Oscillators") (part "osc_xtal_2p_0"))
    )
    (comp (ref "Y2")
      (value "osc_xtal_2p_0")
      (footprint "smd2-0")
      (description "XTAL, 16MHz, 8pF, 50, 20ppm")
      (fields
        (field (name "TOLERANCE") "20ppm")
        (field (name "FREQUENCY") "16M")
        (field (name "PART NUMBER") "OSC-00000")
      )
      (libsource (lib "Oscillators") (part "osc_xtal_2p_0"))
    )
  )
  (nets
    (net (code "2") (name "/I2C_RST") (class "Default")
      (node (ref "U1") (pin "33") (pinfunction "PB12_33") (pintype "passive"))
      (node (ref "U3") (pin "3") (pinfunction "~{RESE}T_3") (pintype "passive"))
    )
    (net (code "3") (name "/I2C_SCL") (class "Default")
      (node (ref "R27") (pin "2") (pinfunction "2_2") (pintype "passive"))
      (node (ref "U1") (pin "37") (pinfunction "PC6_37") (pintype "passive"))
      (node (ref "U3") (pin "22") (pinfunction "SCL_22") (pintype "passive"))
    )
    (net (code "4") (name "/I2C_SDA") (class "Default")
      (node (ref "R26") (pin "2") (pinfunction "2_2") (pintype "passive"))
      (node (ref "U1") (pin "38") (pinfunction "PC7_38") (pintype "passive"))
      (node (ref "U3") (pin "23") (pinfunction "SDA_23") (pintype "passive"))
    )
    (net (code "5") (name "/I2C_SEL0") (class "Default")
      (node (ref "U1") (pin "34") (pinfunction "PB13_34") (pintype "passive"))
      (node (ref "U3") (pin "1") (pinfunction "A0_1") (pintype "passive"))
    )
    (net (code "6") (name "/I2C_SEL1") (class "Default")
      (node (ref "U1") (pin "35") (pinfunction "PB14_35") (pintype "passive"))
      (node (ref "U3") (pin "2") (pinfunction "A1_2") (pintype "passive"))
    )
    (net (code "7") (name "/I2C_SEL2") (class "Default")
      (node (ref "U1") (pin "36") (pinfunction "PB15_36") (pintype "passive"))
      (node (ref "U3") (pin "21") (pinfunction "A2_21") (pintype "passive"))
    )
    (net (code "8") (name "/JTAG_RST") (class "Default")
      (node (ref "P11") (pin "2") (pinfunction "2_2") (pintype "passive"))
      (node (ref "P9") (pin "6") (pinfunction "6_6") (pintype "passive"))
    )
    (net (code "9") (name "/JTAG_TCK") (class "Default")
      (node (ref "P9") (pin "1") (pinfunction "1_1") (pintype "passive"))
      (node (ref "U1") (pin "49") (pinfunction "PA14_49") (pintype "passive"))
    )
    (net (code "10") (name "/JTAG_TMS") (class "Default")
      (node (ref "P9") (pin "5") (pinfunction "5_5") (pintype "passive"))
      (node (ref "U1") (pin "46") (pinfunction "PA13_46") (pintype "passive"))
    )
    (net (code "11") (name "/LED_0") (class "Default")
      (node (ref "R13") (pin "1") (pinfunction "1_1") (pintype "passive"))
      (node (ref "U1") (pin "57") (pinfunction "PB5_57") (pintype "passive"))
    )
    (net (code "12") (name "/LED_1") (class "Default")
      (node (ref "R14") (pin "1") (pinfunction "1_1") (pintype "passive"))
      (node (ref "U1") (pin "56") (pinfunction "PB4_56") (pintype "passive"))
    )
    (net (code "13") (name "/LED_2") (class "Default")
      (node (ref "P9") (pin "3") (pinfunction "3_3") (pintype "passive"))
      (node (ref "R15") (pin "1") (pinfunction "1_1") (pintype "passive"))
      (node (ref "U1") (pin "55") (pinfunction "PB3_55") (pintype "passive"))
    )
    (net (code "14") (name "/LED_3") (class "Default")
      (node (ref "R17") (pin "1") (pinfunction "1_1") (pintype "passive"))
      (node (ref "U1") (pin "54") (pinfunction "PD2_54") (pintype "passive"))
    )
    (net (code "15") (name "/LED_4") (class "Default")
      (node (ref "R18") (pin "1") (pinfunction "1_1") (pintype "passive"))
      (node (ref "U1") (pin "53") (pinfunction "PC12_53") (pintype "passive"))
    )
    (net (code "16") (name "/LED_5") (class "Default")
      (node (ref "R19") (pin "1") (pinfunction "1_1") (pintype "passive"))
      (node (ref "U1") (pin "52") (pinfunction "PC11_52") (pintype "passive"))
    )
    (net (code "17") (name "/LED_6") (class "Default")
      (node (ref "R20") (pin "1") (pinfunction "1_1") (pintype "passive"))
      (node (ref "U1") (pin "51") (pinfunction "PC10_51") (pintype "passive"))
    )
    (net (code "18") (name "/LED_7") (class "Default")
      (node (ref "P9") (pin "9") (pinfunction "9_9") (pintype "passive"))
      (node (ref "R21") (pin "1") (pinfunction "1_1") (pintype "passive"))
      (node (ref "U1") (pin "50") (pinfunction "PA15_50") (pintype "passive"))
    )
    (net (code "19") (name "/M0_PWM0") (class "Default")
      (node (ref "U1") (pin "14") (pinfunction "PA0_14") (pintype "passive"))
      (node (ref "U2") (pin "16") (pinfunction "AIN1_16") (pintype "input"))
    )
    (net (code "20") (name "/M0_PWM1") (class "Default")
      (node (ref "U1") (pin "15") (pinfunction "PA1_15") (pintype "passive"))
      (node (ref "U2") (pin "15") (pinfunction "AIN2_15") (pintype "input"))
    )
    (net (code "21") (name "/M0_QA") (class "Default")
      (node (ref "P4") (pin "4") (pinfunction "4_4") (pintype "passive"))
      (node (ref "U1") (pin "22") (pinfunction "PA6_22") (pintype "passive"))
    )
    (net (code "22") (name "/M0_QB") (class "Default")
      (node (ref "P4") (pin "5") (pinfunction "5_5") (pintype "passive"))
      (node (ref "U1") (pin "23") (pinfunction "PA7_23") (pintype "passive"))
    )
    (net (code "23") (name "/M1_PWM0") (class "Default")
      (node (ref "U1") (pin "17") (pinfunction "PA3_17") (pintype "passive"))
      (node (ref "U2") (pin "9") (pinfunction "BIN1_9") (pintype "input"))
    )
    (net (code "24") (name "/M1_PWM1") (class "Default")
      (node (ref "U1") (pin "16") (pinfunction "PA2_16") (pintype "passive"))
      (node (ref "U2") (pin "10") (pinfunction "BIN2_10") (pintype "input"))
    )
    (net (code "25") (name "/M1_QA") (class "Default")
      (node (ref "P1") (pin "4") (pinfunction "4_4") (pintype "passive"))
      (node (ref "U1") (pin "20") (pinfunction "PA4_20") (pintype "passive"))
    )
    (net (code "26") (name "/M1_QB") (class "Default")
      (node (ref "P1") (pin "5") (pinfunction "5_5") (pintype "passive"))
      (node (ref "U1") (pin "21") (pinfunction "PA5_21") (pintype "passive"))
    )
    (net (code "27") (name "/MD0_A") (class "Default")
      (node (ref "P4") (pin "1") (pinfunction "1_1") (pintype "passive"))
      (node (ref "U2") (pin "2") (pinfunction "AOUT1_2") (pintype "output"))
    )
    (net (code "28") (name "/MD0_B") (class "Default")
      (node (ref "P4") (pin "2") (pinfunction "2_2") (pintype "passive"))
      (node (ref "U2") (pin "4") (pinfunction "AOUT2_4") (pintype "output"))
    )
    (net (code "29") (name "/MD1_A") (class "Default")
      (node (ref "P1") (pin "1") (pinfunction "1_1") (pintype "passive"))
      (node (ref "U2") (pin "7") (pinfunction "BOUT1_7") (pintype "output"))
    )
    (net (code "30") (name "/MD1_B") (class "Default")
      (node (ref "P1") (pin "2") (pinfunction "2_2") (pintype "passive"))
      (node (ref "U2") (pin "5") (pinfunction "BOUT2_5") (pintype "output"))
    )
    (net (code "31") (name "/MX_FAULT") (class "Default")
      (node (ref "R34") (pin "1") (pinfunction "1_1") (pintype "passive"))
      (node (ref "U1") (pin "41") (pinfunction "PA8_41") (pintype "passive"))
      (node (ref "U2") (pin "8") (pinfunction "~{FAULT}_8") (pintype "open_collector"))
    )
    (net (code "32") (name "/OPT_A") (class "Default")
      (node (ref "R8") (pin "1") (pinfunction "1_1") (pintype "passive"))
      (node (ref "SW1") (pin "8") (pinfunction "8_8") (pintype "passive"))
      (node (ref "U1") (pin "26") (pinfunction "PB0_26") (pintype "passive"))
    )
    (net (code "33") (name "/OPT_B") (class "Default")
      (node (ref "R7") (pin "1") (pinfunction "1_1") (pintype "passive"))
      (node (ref "SW1") (pin "7") (pinfunction "7_7") (pintype "passive"))
      (node (ref "U1") (pin "27") (pinfunction "PB1_27") (pintype "passive"))
    )
    (net (code "34") (name "/OPT_C") (class "Default")
      (node (ref "R6") (pin "1") (pinfunction "1_1") (pintype "passive"))
      (node (ref "SW1") (pin "6") (pinfunction "6_6") (pintype "passive"))
      (node (ref "U1") (pin "28") (pinfunction "PB2_28") (pintype "passive"))
    )
    (net (code "35") (name "/OPT_D") (class "Default")
      (node (ref "R5") (pin "1") (pinfunction "1_1") (pintype "passive"))
      (node (ref "SW1") (pin "5") (pinfunction "5_5") (pintype "passive"))
      (node (ref "U1") (pin "29") (pinfunction "PB10_29") (pintype "passive"))
    )
    (net (code "36") (name "/S0_INT") (class "Default")
      (node (ref "P2") (pin "2") (pinfunction "2_2") (pintype "passive"))
      (node (ref "U1") (pin "24") (pinfunction "PC4_24") (pintype "passive"))
    )
    (net (code "37") (name "/S0_SCL") (class "Default")
      (node (ref "P2") (pin "4") (pinfunction "4_4") (pintype "passive"))
      (node (ref "R1") (pin "2") (pinfunction "2_2") (pintype "passive"))
      (node (ref "U3") (pin "5") (pinfunction "SC0_5") (pintype "passive"))
    )
    (net (code "38") (name "/S0_SDA") (class "Default")
      (node (ref "P2") (pin "5") (pinfunction "5_5") (pintype "passive"))
      (node (ref "R2") (pin "2") (pinfunction "2_2") (pintype "passive"))
      (node (ref "U3") (pin "4") (pinfunction "SD0_4") (pintype "passive"))
    )
    (net (code "39") (name "/S0_XS") (class "Default")
      (node (ref "P2") (pin "3") (pinfunction "3_3") (pintype "passive"))
      (node (ref "U1") (pin "25") (pinfunction "PC5_25") (pintype "passive"))
    )
    (net (code "40") (name "/S1_INT") (class "Default")
      (node (ref "P3") (pin "2") (pinfunction "2_2") (pintype "passive"))
      (node (ref "U1") (pin "10") (pinfunction "PC2_10") (pintype "passive"))
    )
    (net (code "41") (name "/S1_SCL") (class "Default")
      (node (ref "P3") (pin "4") (pinfunction "4_4") (pintype "passive"))
      (node (ref "R3") (pin "2") (pinfunction "2_2") (pintype "passive"))
      (node (ref "U3") (pin "7") (pinfunction "SC1_7") (pintype "passive"))
    )
    (net (code "42") (name "/S1_SDA") (class "Default")
      (node (ref "P3") (pin "5") (pinfunction "5_5") (pintype "passive"))
      (node (ref "R4") (pin "2") (pinfunction "2_2") (pintype "passive"))
      (node (ref "U3") (pin "6") (pinfunction "SD1_6") (pintype "passive"))
    )
    (net (code "43") (name "/S1_XS") (class "Default")
      (node (ref "P3") (pin "3") (pinfunction "3_3") (pintype "passive"))
      (node (ref "U1") (pin "11") (pinfunction "PC3_11") (pintype "passive"))
    )
    (net (code "44") (name "/S2_INT") (class "Default")
      (node (ref "P5") (pin "2") (pinfunction "2_2") (pintype "passive"))
      (node (ref "U1") (pin "8") (pinfunction "PC0_8") (pintype "passive"))
    )
    (net (code "45") (name "/S2_SCL") (class "Default")
      (node (ref "P5") (pin "4") (pinfunction "4_4") (pintype "passive"))
      (node (ref "R9") (pin "2") (pinfunction "2_2") (pintype "passive"))
      (node (ref "U3") (pin "9") (pinfunction "SC2_9") (pintype "passive"))
    )
    (net (code "46") (name "/S2_SDA") (class "Default")
      (node (ref "P5") (pin "5") (pinfunction "5_5") (pintype "passive"))
      (node (ref "R10") (pin "2") (pinfunction "2_2") (pintype "passive"))
      (node (ref "U3") (pin "8") (pinfunction "SD2_8") (pintype "passive"))
    )
    (net (code "47") (name "/S2_XS") (class "Default")
      (node (ref "P5") (pin "3") (pinfunction "3_3") (pintype "passive"))
      (node (ref "U1") (pin "9") (pinfunction "PC1_9") (pintype "passive"))
    )
    (net (code "48") (name "/S3_INT") (class "Default")
      (node (ref "P6") (pin "2") (pinfunction "2_2") (pintype "passive"))
      (node (ref "U1") (pin "61") (pinfunction "PB8_61") (pintype "passive"))
    )
    (net (code "49") (name "/S3_SCL") (class "Default")
      (node (ref "P6") (pin "4") (pinfunction "4_4") (pintype "passive"))
      (node (ref "R11") (pin "2") (pinfunction "2_2") (pintype "passive"))
      (node (ref "U3") (pin "11") (pinfunction "SC3_11") (pintype "passive"))
    )
    (net (code "50") (name "/S3_SDA") (class "Default")
      (node (ref "P6") (pin "5") (pinfunction "5_5") (pintype "passive"))
      (node (ref "R12") (pin "2") (pinfunction "2_2") (pintype "passive"))
      (node (ref "U3") (pin "10") (pinfunction "SD3_10") (pintype "passive"))
    )
    (net (code "51") (name "/S3_XS") (class "Default")
      (node (ref "P6") (pin "3") (pinfunction "3_3") (pintype "passive"))
      (node (ref "U1") (pin "62") (pinfunction "PB9_62") (pintype "passive"))
    )
    (net (code "52") (name "/S4_INT") (class "Default")
      (node (ref "P7") (pin "2") (pinfunction "2_2") (pintype "passive"))
      (node (ref "U1") (pin "59") (pinfunction "PB7_59") (pintype "passive"))
    )
    (net (code "53") (name "/S4_SCL") (class "Default")
      (node (ref "P7") (pin "4") (pinfunction "4_4") (pintype "passive"))
      (node (ref "R22") (pin "2") (pinfunction "2_2") (pintype "passive"))
      (node (ref "U3") (pin "14") (pinfunction "SC4_14") (pintype "passive"))
    )
    (net (code "54") (name "/S4_SDA") (class "Default")
      (node (ref "P7") (pin "5") (pinfunction "5_5") (pintype "passive"))
      (node (ref "R23") (pin "2") (pinfunction "2_2") (pintype "passive"))
      (node (ref "U3") (pin "13") (pinfunction "SD4_13") (pintype "passive"))
    )
    (net (code "55") (name "/S4_XS") (class "Default")
      (node (ref "P7") (pin "3") (pinfunction "3_3") (pintype "passive"))
      (node (ref "U1") (pin "58") (pinfunction "PB6_58") (pintype "passive"))
    )
    (net (code "56") (name "/S5_INT") (class "Default")
      (node (ref "P8") (pin "2") (pinfunction "2_2") (pintype "passive"))
      (node (ref "U1") (pin "39") (pinfunction "PC8_39") (pintype "passive"))
    )
    (net (code "57") (name "/S5_SCL") (class "Default")
      (node (ref "P8") (pin "4") (pinfunction "4_4") (pintype "passive"))
      (node (ref "R24") (pin "2") (pinfunction "2_2") (pintype "passive"))
      (node (ref "U3") (pin "16") (pinfunction "SC5_16") (pintype "passive"))
    )
    (net (code "58") (name "/S5_SDA") (class "Default")
      (node (ref "P8") (pin "5") (pinfunction "5_5") (pintype "passive"))
      (node (ref "R25") (pin "2") (pinfunction "2_2") (pintype "passive"))
      (node (ref "U3") (pin "15") (pinfunction "SD5_15") (pintype "passive"))
    )
    (net (code "59") (name "/S5_XS") (class "Default")
      (node (ref "P8") (pin "3") (pinfunction "3_3") (pintype "passive"))
      (node (ref "U1") (pin "40") (pinfunction "PC9_40") (pintype "passive"))
    )
    (net (code "60") (name "GND") (class "Default")
      (node (ref "C1") (pin "2") (pinfunction "2_2") (pintype "passive"))
      (node (ref "C10") (pin "2") (pinfunction "2_2") (pintype "passive"))
      (node (ref "C11") (pin "2") (pinfunction "2_2") (pintype "passive"))
      (node (ref "C12") (pin "2") (pinfunction "2_2") (pintype "passive"))
      (node (ref "C13") (pin "2") (pinfunction "2_2") (pintype "passive"))
      (node (ref "C14") (pin "2") (pinfunction "2_2") (pintype "passive"))
      (node (ref "C15") (pin "2") (pinfunction "2_2") (pintype "passive"))
      (node (ref "C16") (pin "2") (pinfunction "2_2") (pintype "passive"))
      (node (ref "C17") (pin "2") (pinfunction "2_2") (pintype "passive"))
      (node (ref "C18") (pin "2") (pinfunction "2_2") (pintype "passive"))
      (node (ref "C19") (pin "2") (pinfunction "2_2") (pintype "passive"))
      (node (ref "C2") (pin "2") (pinfunction "2_2") (pintype "passive"))
      (node (ref "C20") (pin "2") (pinfunction "2_2") (pintype "passive"))
      (node (ref "C21") (pin "2") (pinfunction "2_2") (pintype "passive"))
      (node (ref "C22") (pin "2") (pinfunction "2_2") (pintype "passive"))
      (node (ref "C23") (pin "2") (pinfunction "2_2") (pintype "passive"))
      (node (ref "C24") (pin "2") (pinfunction "2_2") (pintype "passive"))
      (node (ref "C25") (pin "2") (pinfunction "2_2") (pintype "passive"))
      (node (ref "C26") (pin "2") (pinfunction "2_2") (pintype "passive"))
      (node (ref "C27") (pin "2") (pinfunction "2_2") (pintype "passive"))
      (node (ref "C3") (pin "2") (pinfunction "2_2") (pintype "passive"))
      (node (ref "C4") (pin "2") (pinfunction "2_2") (pintype "passive"))
      (node (ref "C5") (pin "2") (pinfunction "2_2") (pintype "passive"))
      (node (ref "C6") (pin "2") (pinfunction "2_2") (pintype "passive"))
      (node (ref "C7") (pin "2") (pinfunction "2_2") (pintype "passive"))
      (node (ref "C8") (pin "2") (pinfunction "2_2") (pintype "passive"))
      (node (ref "C9") (pin "2") (pinfunction "2_2") (pintype "passive"))
      (node (ref "D1") (pin "1") (pinfunction "1_1") (pintype "passive"))
      (node (ref "D2") (pin "1") (pinfunction "1_1") (pintype "passive"))
      (node (ref "D3") (pin "1") (pinfunction "1_1") (pintype "passive"))
      (node (ref "D4") (pin "1") (pinfunction "1_1") (pintype "passive"))
      (node (ref "D5") (pin "1") (pinfunction "1_1") (pintype "passive"))
      (node (ref "D6") (pin "1") (pinfunction "1_1") (pintype "passive"))
      (node (ref "D7") (pin "1") (pinfunction "1_1") (pintype "passive"))
      (node (ref "D8") (pin "1") (pinfunction "1_1") (pintype "passive"))
      (node (ref "D9") (pin "1") (pinfunction "1_1") (pintype "passive"))
      (node (ref "P1") (pin "6") (pinfunction "6_6") (pintype "passive"))
      (node (ref "P10") (pin "1") (pinfunction "1_1") (pintype "passive"))
      (node (ref "P2") (pin "6") (pinfunction "6_6") (pintype "passive"))
      (node (ref "P3") (pin "6") (pinfunction "6_6") (pintype "passive"))
      (node (ref "P4") (pin "6") (pinfunction "6_6") (pintype "passive"))
      (node (ref "P5") (pin "6") (pinfunction "6_6") (pintype "passive"))
      (node (ref "P6") (pin "6") (pinfunction "6_6") (pintype "passive"))
      (node (ref "P7") (pin "6") (pinfunction "6_6") (pintype "passive"))
      (node (ref "P8") (pin "6") (pinfunction "6_6") (pintype "passive"))
      (node (ref "P9") (pin "10") (pinfunction "10_10") (pintype "passive"))
      (node (ref "Q1") (pin "4") (pinfunction "G_4") (pintype "passive"))
      (node (ref "R16") (pin "2") (pinfunction "2_2") (pintype "passive"))
      (node (ref "R30") (pin "2") (pinfunction "2_2") (pintype "passive"))
      (node (ref "R31") (pin "2") (pinfunction "2_2") (pintype "passive"))
      (node (ref "R5") (pin "2") (pinfunction "2_2") (pintype "passive"))
      (node (ref "R6") (pin "2") (pinfunction "2_2") (pintype "passive"))
      (node (ref "R7") (pin "2") (pinfunction "2_2") (pintype "passive"))
      (node (ref "R8") (pin "2") (pinfunction "2_2") (pintype "passive"))
      (node (ref "SW2") (pin "1") (pinfunction "1_1") (pintype "passive"))
      (node (ref "SW2") (pin "3") (pinfunction "3_3") (pintype "passive"))
      (node (ref "U1") (pin "12") (pinfunction "VSSA/VREF-_12") (pintype "passive"))
      (node (ref "U1") (pin "18") (pinfunction "VSS_18") (pintype "passive"))
      (node (ref "U1") (pin "31") (pinfunction "VSS_31") (pintype "passive"))
      (node (ref "U1") (pin "47") (pinfunction "VSS_47") (pintype "passive"))
      (node (ref "U1") (pin "63") (pinfunction "VSS_63") (pintype "passive"))
      (node (ref "U2") (pin "13") (pinfunction "GND_13") (pintype "power_in"))
      (node (ref "U2") (pin "17") (pinfunction "PGND_17") (pintype "power_in"))
      (node (ref "U3") (pin "12") (pinfunction "VSS_12") (pintype "power_in"))
      (node (ref "U4") (pin "1") (pinfunction "ADJ_1") (pintype "passive"))
    )
    (net (code "61") (name "Net-(D1-Pad2)") (class "Default")
      (node (ref "D1") (pin "2") (pinfunction "2_2") (pintype "passive"))
      (node (ref "R13") (pin "2") (pinfunction "2_2") (pintype "passive"))
    )
    (net (code "62") (name "Net-(D2-Pad2)") (class "Default")
      (node (ref "D2") (pin "2") (pinfunction "2_2") (pintype "passive"))
      (node (ref "R14") (pin "2") (pinfunction "2_2") (pintype "passive"))
    )
    (net (code "63") (name "Net-(D3-Pad2)") (class "Default")
      (node (ref "D3") (pin "2") (pinfunction "2_2") (pintype "passive"))
      (node (ref "R15") (pin "2") (pinfunction "2_2") (pintype "passive"))
    )
    (net (code "64") (name "Net-(D4-Pad2)") (class "Default")
      (node (ref "D4") (pin "2") (pinfunction "2_2") (pintype "passive"))
      (node (ref "R17") (pin "2") (pinfunction "2_2") (pintype "passive"))
    )
    (net (code "65") (name "Net-(D5-Pad2)") (class "Default")
      (node (ref "D5") (pin "2") (pinfunction "2_2") (pintype "passive"))
      (node (ref "R18") (pin "2") (pinfunction "2_2") (pintype "passive"))
    )
    (net (code "66") (name "Net-(D6-Pad2)") (class "Default")
      (node (ref "D6") (pin "2") (pinfunction "2_2") (pintype "passive"))
      (node (ref "R19") (pin "2") (pinfunction "2_2") (pintype "passive"))
    )
    (net (code "67") (name "Net-(D7-Pad2)") (class "Default")
      (node (ref "D7") (pin "2") (pinfunction "2_2") (pintype "passive"))
      (node (ref "R20") (pin "2") (pinfunction "2_2") (pintype "passive"))
    )
    (net (code "68") (name "Net-(D8-Pad2)") (class "Default")
      (node (ref "D8") (pin "2") (pinfunction "2_2") (pintype "passive"))
      (node (ref "R21") (pin "2") (pinfunction "2_2") (pintype "passive"))
    )
    (net (code "69") (name "Net-(D9-Pad2)") (class "Default")
      (node (ref "D9") (pin "2") (pinfunction "2_2") (pintype "passive"))
      (node (ref "R28") (pin "2") (pinfunction "2_2") (pintype "passive"))
    )
    (net (code "70") (name "Net-(P10-Pad2)") (class "Default")
      (node (ref "P10") (pin "2") (pinfunction "2_2") (pintype "passive"))
      (node (ref "SW3") (pin "2") (pinfunction "2_2") (pintype "passive"))
    )
    (net (code "71") (name "Net-(P11-Pad1)") (class "Default")
      (node (ref "P11") (pin "1") (pinfunction "1_1") (pintype "passive"))
      (node (ref "R37") (pin "2") (pinfunction "2_2") (pintype "passive"))
    )
    (net (code "72") (name "Net-(Q1-D-Pad5)") (class "Default")
      (node (ref "Q1") (pin "5") (pinfunction "D_5") (pintype "passive"))
      (node (ref "Q1") (pin "6") (pinfunction "D_6") (pintype "passive"))
      (node (ref "Q1") (pin "7") (pinfunction "D_7") (pintype "passive"))
      (node (ref "Q1") (pin "8") (pinfunction "D_8") (pintype "passive"))
      (node (ref "SW3") (pin "3") (pinfunction "3_3") (pintype "passive"))
    )
    (net (code "73") (name "Net-(U1-BOOT0)") (class "Default")
      (node (ref "R16") (pin "1") (pinfunction "1_1") (pintype "passive"))
      (node (ref "U1") (pin "60") (pinfunction "BOOT0_60") (pintype "passive"))
    )
    (net (code "74") (name "Net-(U1-NRST)") (class "Default")
      (node (ref "C13") (pin "1") (pinfunction "1_1") (pintype "passive"))
      (node (ref "R37") (pin "1") (pinfunction "1_1") (pintype "passive"))
      (node (ref "SW2") (pin "2") (pinfunction "2_2") (pintype "passive"))
      (node (ref "SW2") (pin "4") (pinfunction "4_4") (pintype "passive"))
      (node (ref "U1") (pin "7") (pinfunction "NRST_7") (pintype "passive"))
    )
    (net (code "75") (name "Net-(U1-PC14-OSC32_IN)") (class "Default")
      (node (ref "C9") (pin "1") (pinfunction "1_1") (pintype "passive"))
      (node (ref "U1") (pin "3") (pinfunction "PC14-OSC32_IN_3") (pintype "passive"))
      (node (ref "Y1") (pin "1") (pinfunction "20_1") (pintype "passive"))
    )
    (net (code "76") (name "Net-(U1-PC15-OSC32_OUT)") (class "Default")
      (node (ref "C10") (pin "1") (pinfunction "1_1") (pintype "passive"))
      (node (ref "U1") (pin "4") (pinfunction "PC15-OSC32_OUT_4") (pintype "passive"))
      (node (ref "Y1") (pin "2") (pinfunction "20_2") (pintype "passive"))
    )
    (net (code "77") (name "Net-(U1-PH0-OSC_IN)") (class "Default")
      (node (ref "C11") (pin "1") (pinfunction "1_1") (pintype "passive"))
      (node (ref "U1") (pin "5") (pinfunction "PH0-OSC_IN_5") (pintype "passive"))
      (node (ref "Y2") (pin "1") (pinfunction "20_1") (pintype "passive"))
    )
    (net (code "78") (name "Net-(U1-PH1-OSC_OUT)") (class "Default")
      (node (ref "C12") (pin "1") (pinfunction "1_1") (pintype "passive"))
      (node (ref "U1") (pin "6") (pinfunction "PH1-OSC_OUT_6") (pintype "passive"))
      (node (ref "Y2") (pin "2") (pinfunction "20_2") (pintype "passive"))
    )
    (net (code "79") (name "Net-(U2-AISEN)") (class "Default")
      (node (ref "R31") (pin "1") (pinfunction "1_1") (pintype "passive"))
      (node (ref "U2") (pin "3") (pinfunction "AISEN_3") (pintype "input"))
    )
    (net (code "80") (name "Net-(U2-BISEN)") (class "Default")
      (node (ref "R30") (pin "1") (pinfunction "1_1") (pintype "passive"))
      (node (ref "U2") (pin "6") (pinfunction "BISEN_6") (pintype "input"))
    )
    (net (code "81") (name "Net-(U2-VINT)") (class "Default")
      (node (ref "C18") (pin "1") (pinfunction "1_1") (pintype "passive"))
      (node (ref "U2") (pin "11") (pinfunction "VREF_11") (pintype "passive"))
      (node (ref "U2") (pin "14") (pinfunction "VINT_14") (pintype "passive"))
    )
    (net (code "82") (name "Net-(U2-~{SLEEP})") (class "Default")
      (node (ref "R33") (pin "1") (pinfunction "1_1") (pintype "passive"))
      (node (ref "U2") (pin "1") (pinfunction "~{SLEEP}_1") (pintype "input"))
    )
    (net (code "83") (name "Net-(U3-SC6)") (class "Default")
      (node (ref "R32") (pin "1") (pinfunction "1_1") (pintype "passive"))
      (node (ref "U3") (pin "18") (pinfunction "SC6_18") (pintype "passive"))
    )
    (net (code "84") (name "Net-(U3-SC7)") (class "Default")
      (node (ref "R36") (pin "1") (pinfunction "1_1") (pintype "passive"))
      (node (ref "U3") (pin "20") (pinfunction "SC7_20") (pintype "passive"))
    )
    (net (code "85") (name "Net-(U3-SD6)") (class "Default")
      (node (ref "R29") (pin "1") (pinfunction "1_1") (pintype "passive"))
      (node (ref "U3") (pin "17") (pinfunction "SD6_17") (pintype "passive"))
    )
    (net (code "86") (name "Net-(U3-SD7)") (class "Default")
      (node (ref "R35") (pin "1") (pinfunction "1_1") (pintype "passive"))
      (node (ref "U3") (pin "19") (pinfunction "SD7_19") (pintype "passive"))
    )
    (net (code "87") (name "VBAT_SWITCHED") (class "Default")
      (node (ref "C14") (pin "1") (pinfunction "1_1") (pintype "passive"))
      (node (ref "C15") (pin "1") (pinfunction "1_1") (pintype "passive"))
      (node (ref "C16") (pin "1") (pinfunction "1_1") (pintype "passive"))
      (node (ref "C17") (pin "1") (pinfunction "1_1") (pintype "passive"))
      (node (ref "Q1") (pin "1") (pinfunction "S_1") (pintype "passive"))
      (node (ref "Q1") (pin "2") (pinfunction "S_2") (pintype "passive"))
      (node (ref "Q1") (pin "3") (pinfunction "S_3") (pintype "passive"))
      (node (ref "U2") (pin "12") (pinfunction "VM_12") (pintype "power_in"))
      (node (ref "U4") (pin "3") (pinfunction "VIN_3") (pintype "passive"))
    )
    (net (code "88") (name "VCC") (class "Default")
      (node (ref "C1") (pin "1") (pinfunction "1_1") (pintype "passive"))
      (node (ref "C19") (pin "1") (pinfunction "1_1") (pintype "passive"))
      (node (ref "C2") (pin "1") (pinfunction "1_1") (pintype "passive"))
      (node (ref "C20") (pin "1") (pinfunction "1_1") (pintype "passive"))
      (node (ref "C21") (pin "1") (pinfunction "1_1") (pintype "passive"))
      (node (ref "C22") (pin "1") (pinfunction "1_1") (pintype "passive"))
      (node (ref "C23") (pin "1") (pinfunction "1_1") (pintype "passive"))
      (node (ref "C24") (pin "1") (pinfunction "1_1") (pintype "passive"))
      (node (ref "C25") (pin "1") (pinfunction "1_1") (pintype "passive"))
      (node (ref "C26") (pin "1") (pinfunction "1_1") (pintype "passive"))
      (node (ref "C27") (pin "1") (pinfunction "1_1") (pintype "passive"))
      (node (ref "C3") (pin "1") (pinfunction "1_1") (pintype "passive"))
      (node (ref "C4") (pin "1") (pinfunction "1_1") (pintype "passive"))
      (node (ref "C5") (pin "1") (pinfunction "1_1") (pintype "passive"))
      (node (ref "C6") (pin "1") (pinfunction "1_1") (pintype "passive"))
      (node (ref "C7") (pin "1") (pinfunction "1_1") (pintype "passive"))
      (node (ref "C8") (pin "1") (pinfunction "1_1") (pintype "passive"))
      (node (ref "P1") (pin "3") (pinfunction "3_3") (pintype "passive"))
      (node (ref "P2") (pin "1") (pinfunction "1_1") (pintype "passive"))
      (node (ref "P3") (pin "1") (pinfunction "1_1") (pintype "passive"))
      (node (ref "P4") (pin "3") (pinfunction "3_3") (pintype "passive"))
      (node (ref "P5") (pin "1") (pinfunction "1_1") (pintype "passive"))
      (node (ref "P6") (pin "1") (pinfunction "1_1") (pintype "passive"))
      (node (ref "P7") (pin "1") (pinfunction "1_1") (pintype "passive"))
      (node (ref "P8") (pin "1") (pinfunction "1_1") (pintype "passive"))
      (node (ref "P9") (pin "4") (pinfunction "4_4") (pintype "passive"))
      (node (ref "R1") (pin "1") (pinfunction "1_1") (pintype "passive"))
      (node (ref "R10") (pin "1") (pinfunction "1_1") (pintype "passive"))
      (node (ref "R11") (pin "1") (pinfunction "1_1") (pintype "passive"))
      (node (ref "R12") (pin "1") (pinfunction "1_1") (pintype "passive"))
      (node (ref "R2") (pin "1") (pinfunction "1_1") (pintype "passive"))
      (node (ref "R22") (pin "1") (pinfunction "1_1") (pintype "passive"))
      (node (ref "R23") (pin "1") (pinfunction "1_1") (pintype "passive"))
      (node (ref "R24") (pin "1") (pinfunction "1_1") (pintype "passive"))
      (node (ref "R25") (pin "1") (pinfunction "1_1") (pintype "passive"))
      (node (ref "R26") (pin "1") (pinfunction "1_1") (pintype "passive"))
      (node (ref "R27") (pin "1") (pinfunction "1_1") (pintype "passive"))
      (node (ref "R28") (pin "1") (pinfunction "1_1") (pintype "passive"))
      (node (ref "R29") (pin "2") (pinfunction "2_2") (pintype "passive"))
      (node (ref "R3") (pin "1") (pinfunction "1_1") (pintype "passive"))
      (node (ref "R32") (pin "2") (pinfunction "2_2") (pintype "passive"))
      (node (ref "R33") (pin "2") (pinfunction "2_2") (pintype "passive"))
      (node (ref "R34") (pin "2") (pinfunction "2_2") (pintype "passive"))
      (node (ref "R35") (pin "2") (pinfunction "2_2") (pintype "passive"))
      (node (ref "R36") (pin "2") (pinfunction "2_2") (pintype "passive"))
      (node (ref "R4") (pin "1") (pinfunction "1_1") (pintype "passive"))
      (node (ref "R9") (pin "1") (pinfunction "1_1") (pintype "passive"))
      (node (ref "SW1") (pin "1") (pinfunction "1_1") (pintype "passive"))
      (node (ref "SW1") (pin "2") (pinfunction "2_2") (pintype "passive"))
      (node (ref "SW1") (pin "3") (pinfunction "3_3") (pintype "passive"))
      (node (ref "SW1") (pin "4") (pinfunction "4_4") (pintype "passive"))
      (node (ref "U1") (pin "1") (pinfunction "VBAT_1") (pintype "passive"))
      (node (ref "U1") (pin "13") (pinfunction "VDDA/VREF+_13") (pintype "passive"))
      (node (ref "U1") (pin "19") (pinfunction "VDD_19") (pintype "passive"))
      (node (ref "U1") (pin "30") (pinfunction "VCAP_1_30") (pintype "passive"))
      (node (ref "U1") (pin "32") (pinfunction "VDD_32") (pintype "passive"))
      (node (ref "U1") (pin "48") (pinfunction "VDD_48") (pintype "passive"))
      (node (ref "U1") (pin "64") (pinfunction "VDD_64") (pintype "passive"))
      (node (ref "U3") (pin "24") (pinfunction "VDD_24") (pintype "power_in"))
      (node (ref "U4") (pin "2") (pinfunction "VOUT_2") (pintype "passive"))
      (node (ref "U4") (pin "4") (pinfunction "VOUT_4") (pintype "passive"))
    )
    (net (code "89") (name "unconnected-(P9-Pad2)") (class "Default")
      (node (ref "P9") (pin "2") (pinfunction "2_2") (pintype "passive"))
    )
    (net (code "90") (name "unconnected-(P9-Pad7)") (class "Default")
      (node (ref "P9") (pin "7") (pinfunction "7_7") (pintype "passive"))
    )
    (net (code "91") (name "unconnected-(P9-Pad8)") (class "Default")
      (node (ref "P9") (pin "8") (pinfunction "8_8") (pintype "passive"))
    )
    (net (code "92") (name "unconnected-(SW3-Pad1)") (class "Default")
      (node (ref "SW3") (pin "1") (pinfunction "1_1") (pintype "passive+no_connect"))
    )
    (net (code "93") (name "unconnected-(U1-PA9-Pad42)") (class "Default")
      (node (ref "U1") (pin "42") (pinfunction "PA9_42") (pintype "passive+no_connect"))
    )
    (net (code "94") (name "unconnected-(U1-PA10-Pad43)") (class "Default")
      (node (ref "U1") (pin "43") (pinfunction "PA10_43") (pintype "passive+no_connect"))
    )
    (net (code "95") (name "unconnected-(U1-PA11-Pad44)") (class "Default")
      (node (ref "U1") (pin "44") (pinfunction "PA11_44") (pintype "passive+no_connect"))
    )
    (net (code "96") (name "unconnected-(U1-PA12-Pad45)") (class "Default")
      (node (ref "U1") (pin "45") (pinfunction "PA12_45") (pintype "passive+no_connect"))
    )
    (net (code "97") (name "unconnected-(U1-PC13-Pad2)") (class "Default")
      (node (ref "U1") (pin "2") (pinfunction "PC13_2") (pintype "passive+no_connect"))
    )
  )
)
